# main.net
KiCad netlist of a schematic drawn in EAGLE
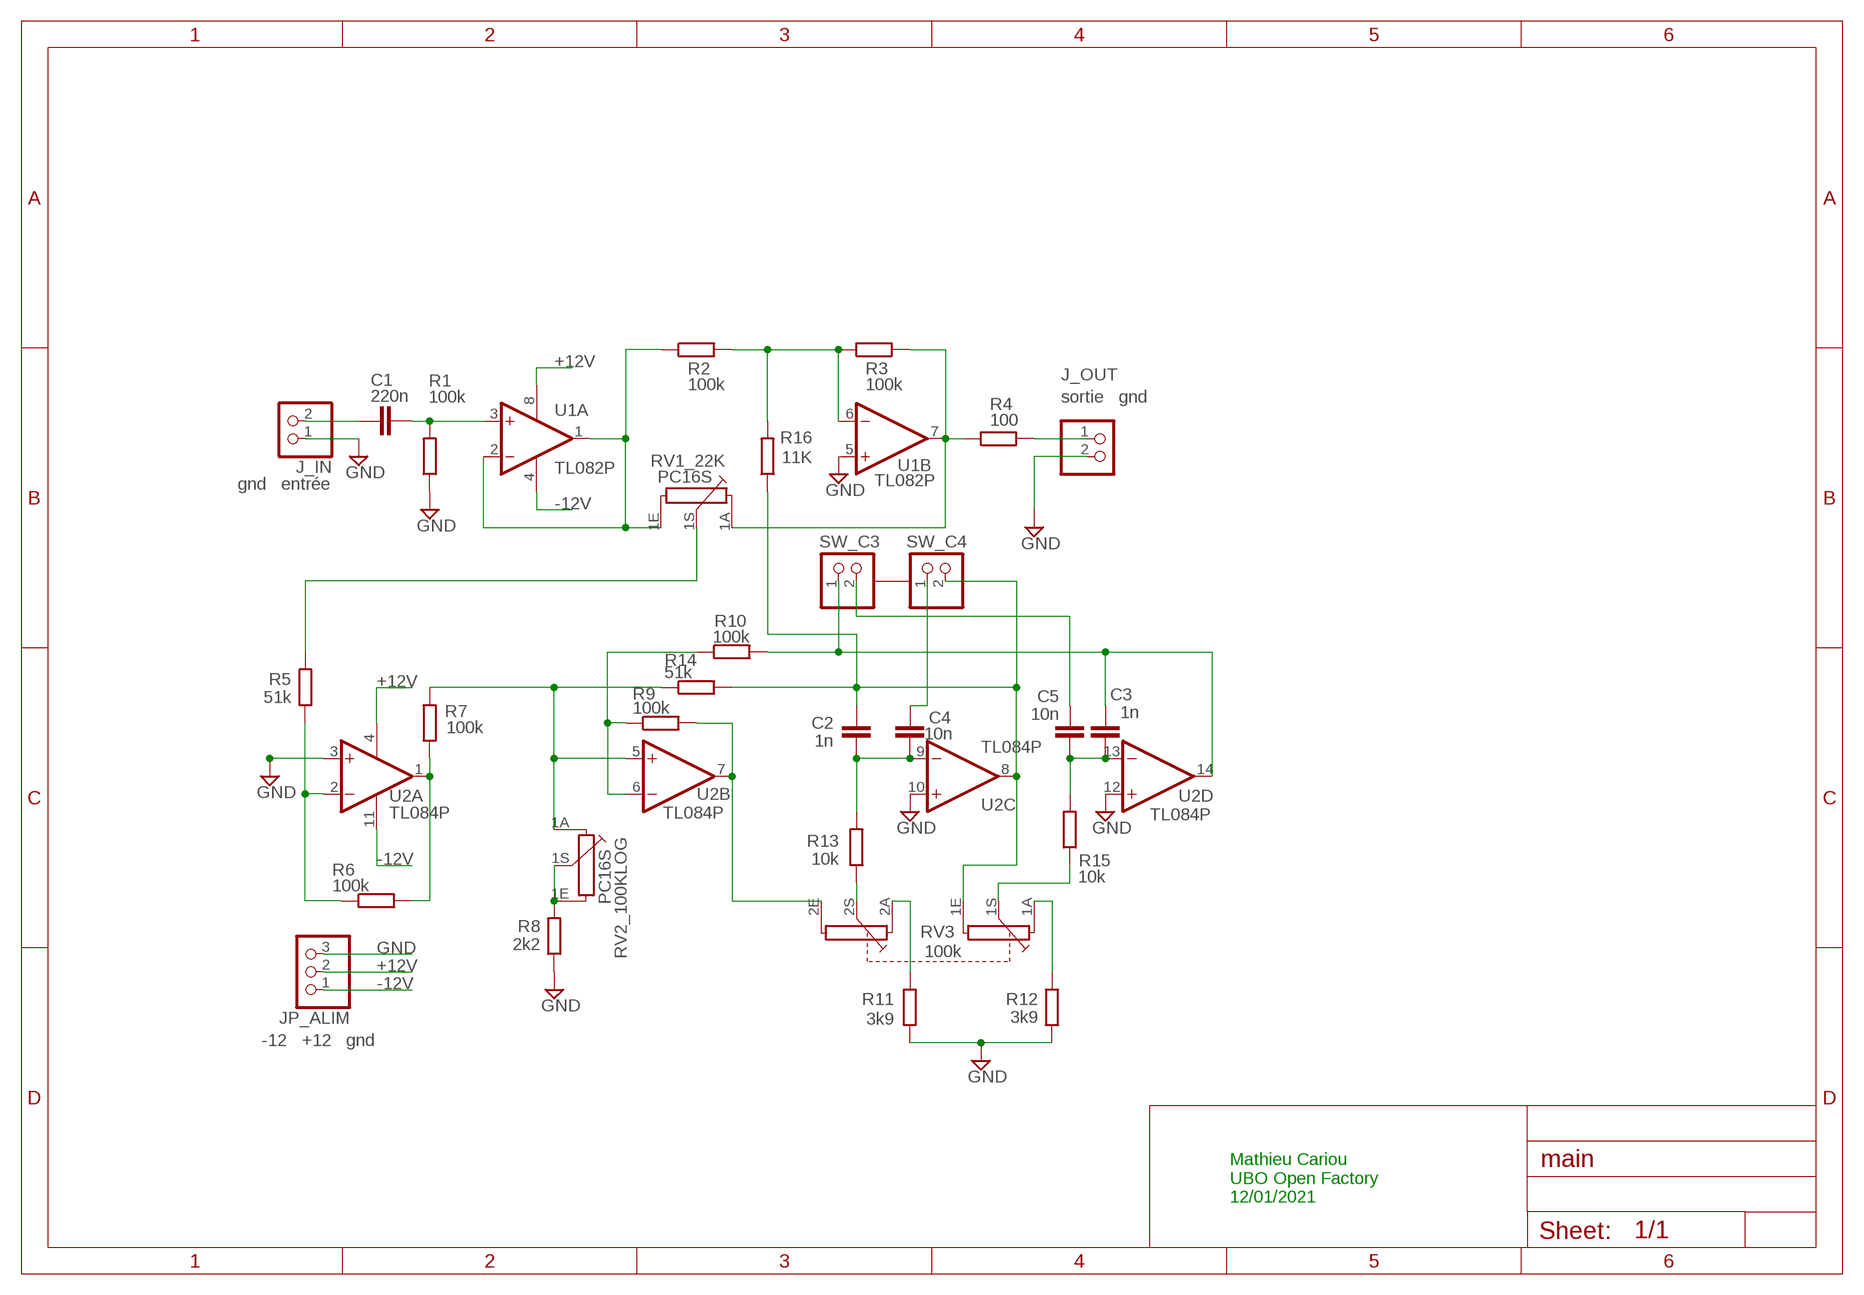
[diagram p0: schematic, sheet 1]

(export (version "E")
  (design (tool "Eeschema 10.0.6"))
  (components
    (comp (ref "C1")
      (value "220n")
      (footprint "eagle-import:C050-030X075")
      (libsource (lib "eagle-import") (part "C-EU050-030X075"))
    )
    (comp (ref "C2")
      (value "1n")
      (footprint "eagle-import:C050-030X075")
      (libsource (lib "eagle-import") (part "C-EU050-030X075"))
    )
    (comp (ref "C3")
      (value "1n")
      (footprint "eagle-import:C050-030X075")
      (libsource (lib "eagle-import") (part "C-EU050-030X075"))
    )
    (comp (ref "C4")
      (value "10n")
      (footprint "eagle-import:C050-030X075")
      (libsource (lib "eagle-import") (part "C-EU050-030X075"))
    )
    (comp (ref "C5")
      (value "10n")
      (footprint "eagle-import:C050-030X075")
      (libsource (lib "eagle-import") (part "C-EU050-030X075"))
    )
    (comp (ref "JP_ALIM")
      (value "-12 +12 gnd")
      (footprint "eagle-import:1X03")
      (libsource (lib "eagle-import") (part "PINHD-1X3"))
    )
    (comp (ref "J_IN")
      (value "gnd entrée")
      (footprint "eagle-import:1X02")
      (libsource (lib "eagle-import") (part "PINHD-1X2"))
    )
    (comp (ref "J_OUT")
      (value "sortie gnd")
      (footprint "eagle-import:1X02")
      (libsource (lib "eagle-import") (part "PINHD-1X2"))
    )
    (comp (ref "R1")
      (value "100k")
      (footprint "eagle-import:0204_7")
      (libsource (lib "eagle-import") (part "R-EU_0204/7"))
    )
    (comp (ref "R2")
      (value "100k")
      (footprint "eagle-import:0204_7")
      (libsource (lib "eagle-import") (part "R-EU_0204/7"))
    )
    (comp (ref "R3")
      (value "100k")
      (footprint "eagle-import:0204_7")
      (libsource (lib "eagle-import") (part "R-EU_0204/7"))
    )
    (comp (ref "R4")
      (value "100")
      (footprint "eagle-import:0204_7")
      (libsource (lib "eagle-import") (part "R-EU_0204/7"))
    )
    (comp (ref "R5")
      (value "51k")
      (footprint "eagle-import:0204_7")
      (libsource (lib "eagle-import") (part "R-EU_0204/7"))
    )
    (comp (ref "R6")
      (value "100k")
      (footprint "eagle-import:0204_7")
      (libsource (lib "eagle-import") (part "R-EU_0204/7"))
    )
    (comp (ref "R7")
      (value "100k")
      (footprint "eagle-import:0204_7")
      (libsource (lib "eagle-import") (part "R-EU_0204/7"))
    )
    (comp (ref "R8")
      (value "2k2")
      (footprint "eagle-import:0204_7")
      (libsource (lib "eagle-import") (part "R-EU_0204/7"))
    )
    (comp (ref "R9")
      (value "100k")
      (footprint "eagle-import:0204_7")
      (libsource (lib "eagle-import") (part "R-EU_0204/7"))
    )
    (comp (ref "R10")
      (value "100k")
      (footprint "eagle-import:0204_7")
      (libsource (lib "eagle-import") (part "R-EU_0204/7"))
    )
    (comp (ref "R11")
      (value "3k9")
      (footprint "eagle-import:0204_7")
      (libsource (lib "eagle-import") (part "R-EU_0204/7"))
    )
    (comp (ref "R12")
      (value "3k9")
      (footprint "eagle-import:0204_7")
      (libsource (lib "eagle-import") (part "R-EU_0204/7"))
    )
    (comp (ref "R13")
      (value "10k")
      (footprint "eagle-import:0204_7")
      (libsource (lib "eagle-import") (part "R-EU_0204/7"))
    )
    (comp (ref "R14")
      (value "51k")
      (footprint "eagle-import:0204_7")
      (libsource (lib "eagle-import") (part "R-EU_0204/7"))
    )
    (comp (ref "R15")
      (value "10k")
      (footprint "eagle-import:0204_7")
      (libsource (lib "eagle-import") (part "R-EU_0204/7"))
    )
    (comp (ref "R16")
      (value "11K")
      (footprint "eagle-import:0204_7")
      (libsource (lib "eagle-import") (part "R-EU_0204/7"))
    )
    (comp (ref "RV1_22K")
      (value "PC16S")
      (footprint "eagle-import:PC16S")
      (libsource (lib "eagle-import") (part "PC16S"))
    )
    (comp (ref "RV2_100KLOG")
      (value "PC16S")
      (footprint "eagle-import:PC16S")
      (libsource (lib "eagle-import") (part "PC16S"))
    )
    (comp (ref "RV3")
      (value "100k")
      (footprint "eagle-import:PC16D")
      (libsource (lib "eagle-import") (part "PC16D"))
    )
    (comp (ref "SW_C3")
      (value "PINHD-1X2")
      (footprint "eagle-import:1X02")
      (libsource (lib "eagle-import") (part "PINHD-1X2"))
    )
    (comp (ref "SW_C4")
      (value "PINHD-1X2")
      (footprint "eagle-import:1X02")
      (libsource (lib "eagle-import") (part "PINHD-1X2"))
    )
    (comp (ref "U1")
      (value "TL082P")
      (footprint "eagle-import:DIL08")
      (libsource (lib "eagle-import") (part "TL082P"))
    )
    (comp (ref "U2")
      (value "TL084P")
      (footprint "eagle-import:DIL14")
      (libsource (lib "eagle-import") (part "TL084P"))
    )
  )
  (nets
    (net (code "1") (name "/+12V") (class "Default")
      (node (ref "JP_ALIM") (pin "2") (pinfunction "2_2") (pintype "passive"))
      (node (ref "U1") (pin "8") (pinfunction "V+_8") (pintype "power_in"))
      (node (ref "U2") (pin "4") (pinfunction "V+_4") (pintype "power_in"))
    )
    (net (code "2") (name "/-12V") (class "Default")
      (node (ref "JP_ALIM") (pin "1") (pinfunction "1_1") (pintype "passive"))
      (node (ref "U1") (pin "4") (pinfunction "V-_4") (pintype "power_in"))
      (node (ref "U2") (pin "11") (pinfunction "V-_11") (pintype "power_in"))
    )
    (net (code "3") (name "GND") (class "Default")
      (node (ref "JP_ALIM") (pin "3") (pinfunction "3_3") (pintype "passive"))
      (node (ref "J_IN") (pin "1") (pinfunction "1_1") (pintype "passive"))
      (node (ref "J_OUT") (pin "2") (pinfunction "2_2") (pintype "passive"))
      (node (ref "R1") (pin "1") (pinfunction "1_1") (pintype "passive"))
      (node (ref "R11") (pin "1") (pinfunction "1_1") (pintype "passive"))
      (node (ref "R12") (pin "1") (pinfunction "1_1") (pintype "passive"))
      (node (ref "R8") (pin "1") (pinfunction "1_1") (pintype "passive"))
      (node (ref "U1") (pin "5") (pinfunction "+IN_5") (pintype "input"))
      (node (ref "U2") (pin "10") (pinfunction "+IN_10") (pintype "input"))
      (node (ref "U2") (pin "12") (pinfunction "+IN_12") (pintype "input"))
      (node (ref "U2") (pin "3") (pinfunction "+IN_3") (pintype "input"))
    )
    (net (code "4") (name "Net-(C1-Pad1)") (class "Default")
      (node (ref "C1") (pin "1") (pinfunction "1_1") (pintype "passive"))
      (node (ref "J_IN") (pin "2") (pinfunction "2_2") (pintype "passive"))
    )
    (net (code "5") (name "Net-(C4-Pad2)") (class "Default")
      (node (ref "C4") (pin "2") (pinfunction "2_2") (pintype "passive"))
      (node (ref "SW_C4") (pin "1") (pinfunction "1_1") (pintype "passive"))
    )
    (net (code "6") (name "Net-(C5-Pad2)") (class "Default")
      (node (ref "C5") (pin "2") (pinfunction "2_2") (pintype "passive"))
      (node (ref "SW_C3") (pin "2") (pinfunction "2_2") (pintype "passive"))
    )
    (net (code "7") (name "Net-(J_OUT-Pad1)") (class "Default")
      (node (ref "J_OUT") (pin "1") (pinfunction "1_1") (pintype "passive"))
      (node (ref "R4") (pin "2") (pinfunction "2_2") (pintype "passive"))
    )
    (net (code "8") (name "Net-(R5-Pad2)") (class "Default")
      (node (ref "R5") (pin "2") (pinfunction "2_2") (pintype "passive"))
      (node (ref "RV1_22K") (pin "1S") (pinfunction "1S_1S") (pintype "passive"))
    )
    (net (code "9") (name "Net-(R8-Pad2)") (class "Default")
      (node (ref "R8") (pin "2") (pinfunction "2_2") (pintype "passive"))
      (node (ref "RV2_100KLOG") (pin "1E") (pinfunction "1E_1E") (pintype "passive"))
      (node (ref "RV2_100KLOG") (pin "1S") (pinfunction "1S_1S") (pintype "passive"))
    )
    (net (code "10") (name "Net-(R11-Pad2)") (class "Default")
      (node (ref "R11") (pin "2") (pinfunction "2_2") (pintype "passive"))
      (node (ref "RV3") (pin "2A") (pinfunction "2A_2A") (pintype "passive"))
    )
    (net (code "11") (name "Net-(R12-Pad2)") (class "Default")
      (node (ref "R12") (pin "2") (pinfunction "2_2") (pintype "passive"))
      (node (ref "RV3") (pin "1A") (pinfunction "1A_1A") (pintype "passive"))
    )
    (net (code "12") (name "Net-(R13-Pad1)") (class "Default")
      (node (ref "R13") (pin "1") (pinfunction "1_1") (pintype "passive"))
      (node (ref "RV3") (pin "2S") (pinfunction "2S_2S") (pintype "passive"))
    )
    (net (code "13") (name "Net-(R15-Pad1)") (class "Default")
      (node (ref "R15") (pin "1") (pinfunction "1_1") (pintype "passive"))
      (node (ref "RV3") (pin "1S") (pinfunction "1S_1S") (pintype "passive"))
    )
    (net (code "14") (name "Net-(U1A-+IN)") (class "Default")
      (node (ref "C1") (pin "2") (pinfunction "2_2") (pintype "passive"))
      (node (ref "R1") (pin "2") (pinfunction "2_2") (pintype "passive"))
      (node (ref "U1") (pin "3") (pinfunction "+IN_3") (pintype "input"))
    )
    (net (code "15") (name "Net-(U1A--IN)") (class "Default")
      (node (ref "R2") (pin "1") (pinfunction "1_1") (pintype "passive"))
      (node (ref "RV1_22K") (pin "1E") (pinfunction "1E_1E") (pintype "passive"))
      (node (ref "U1") (pin "1") (pinfunction "OUT_1") (pintype "output"))
      (node (ref "U1") (pin "2") (pinfunction "-IN_2") (pintype "input"))
    )
    (net (code "16") (name "Net-(U1B--IN)") (class "Default")
      (node (ref "R16") (pin "2") (pinfunction "2_2") (pintype "passive"))
      (node (ref "R2") (pin "2") (pinfunction "2_2") (pintype "passive"))
      (node (ref "R3") (pin "1") (pinfunction "1_1") (pintype "passive"))
      (node (ref "U1") (pin "6") (pinfunction "-IN_6") (pintype "input"))
    )
    (net (code "17") (name "Net-(U1B-OUT)") (class "Default")
      (node (ref "R3") (pin "2") (pinfunction "2_2") (pintype "passive"))
      (node (ref "R4") (pin "1") (pinfunction "1_1") (pintype "passive"))
      (node (ref "RV1_22K") (pin "1A") (pinfunction "1A_1A") (pintype "passive"))
      (node (ref "U1") (pin "7") (pinfunction "OUT_7") (pintype "output"))
    )
    (net (code "18") (name "Net-(U2A--IN)") (class "Default")
      (node (ref "R5") (pin "1") (pinfunction "1_1") (pintype "passive"))
      (node (ref "R6") (pin "1") (pinfunction "1_1") (pintype "passive"))
      (node (ref "U2") (pin "2") (pinfunction "-IN_2") (pintype "input"))
    )
    (net (code "19") (name "Net-(U2A-OUT)") (class "Default")
      (node (ref "R6") (pin "2") (pinfunction "2_2") (pintype "passive"))
      (node (ref "R7") (pin "1") (pinfunction "1_1") (pintype "passive"))
      (node (ref "U2") (pin "1") (pinfunction "OUT_1") (pintype "output"))
    )
    (net (code "20") (name "Net-(U2B-+IN)") (class "Default")
      (node (ref "R14") (pin "1") (pinfunction "1_1") (pintype "passive"))
      (node (ref "R7") (pin "2") (pinfunction "2_2") (pintype "passive"))
      (node (ref "RV2_100KLOG") (pin "1A") (pinfunction "1A_1A") (pintype "passive"))
      (node (ref "U2") (pin "5") (pinfunction "+IN_5") (pintype "input"))
    )
    (net (code "21") (name "Net-(U2B--IN)") (class "Default")
      (node (ref "R10") (pin "1") (pinfunction "1_1") (pintype "passive"))
      (node (ref "R9") (pin "1") (pinfunction "1_1") (pintype "passive"))
      (node (ref "U2") (pin "6") (pinfunction "-IN_6") (pintype "input"))
    )
    (net (code "22") (name "Net-(U2B-OUT)") (class "Default")
      (node (ref "R9") (pin "2") (pinfunction "2_2") (pintype "passive"))
      (node (ref "RV3") (pin "2E") (pinfunction "2E_2E") (pintype "passive"))
      (node (ref "U2") (pin "7") (pinfunction "OUT_7") (pintype "output"))
    )
    (net (code "23") (name "Net-(U2C--IN)") (class "Default")
      (node (ref "C2") (pin "1") (pinfunction "1_1") (pintype "passive"))
      (node (ref "C4") (pin "1") (pinfunction "1_1") (pintype "passive"))
      (node (ref "R13") (pin "2") (pinfunction "2_2") (pintype "passive"))
      (node (ref "U2") (pin "9") (pinfunction "-IN_9") (pintype "input"))
    )
    (net (code "24") (name "Net-(U2C-OUT)") (class "Default")
      (node (ref "C2") (pin "2") (pinfunction "2_2") (pintype "passive"))
      (node (ref "R14") (pin "2") (pinfunction "2_2") (pintype "passive"))
      (node (ref "R16") (pin "1") (pinfunction "1_1") (pintype "passive"))
      (node (ref "RV3") (pin "1E") (pinfunction "1E_1E") (pintype "passive"))
      (node (ref "SW_C4") (pin "2") (pinfunction "2_2") (pintype "passive"))
      (node (ref "U2") (pin "8") (pinfunction "OUT_8") (pintype "output"))
    )
    (net (code "25") (name "Net-(U2D--IN)") (class "Default")
      (node (ref "C3") (pin "1") (pinfunction "1_1") (pintype "passive"))
      (node (ref "C5") (pin "1") (pinfunction "1_1") (pintype "passive"))
      (node (ref "R15") (pin "2") (pinfunction "2_2") (pintype "passive"))
      (node (ref "U2") (pin "13") (pinfunction "-IN_13") (pintype "input"))
    )
    (net (code "26") (name "Net-(U2D-OUT)") (class "Default")
      (node (ref "C3") (pin "2") (pinfunction "2_2") (pintype "passive"))
      (node (ref "R10") (pin "2") (pinfunction "2_2") (pintype "passive"))
      (node (ref "SW_C3") (pin "1") (pinfunction "1_1") (pintype "passive"))
      (node (ref "U2") (pin "14") (pinfunction "OUT_14") (pintype "output"))
    )
  )
)
